# LEDs_and_Buttons.net
KiCad netlist of a schematic drawn in EAGLE
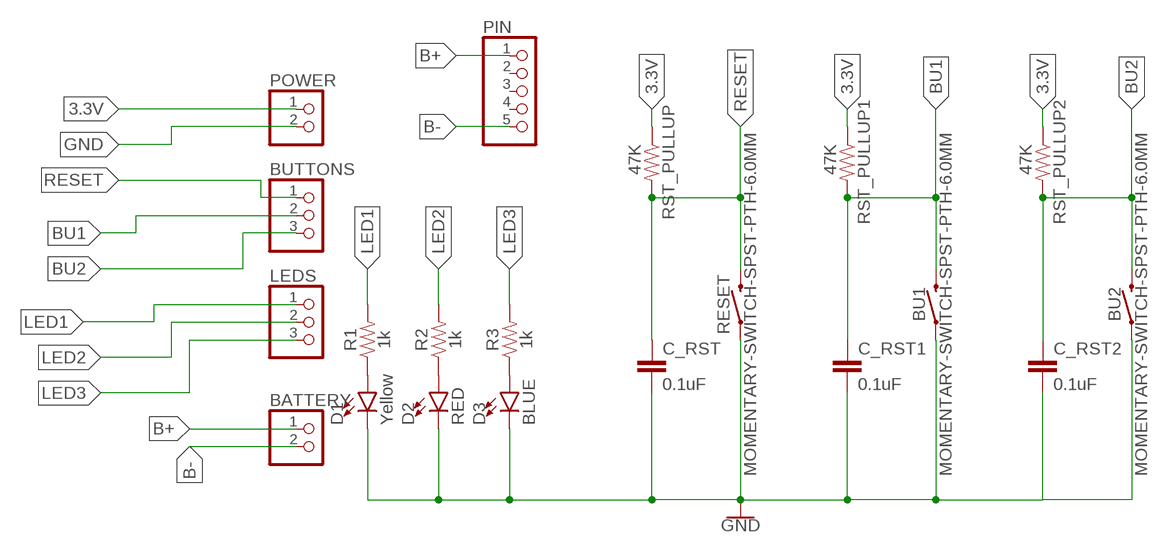
[diagram p0: schematic, sheet 1]

(export (version "E")
  (design (tool "Eeschema 10.0.6"))
  (components
    (comp (ref "BATTERY")
      (value "PINHD-1X2")
      (footprint "eagle-import:1X02")
      (libsource (lib "eagle-import") (part "PINHD-1X2"))
    )
    (comp (ref "BU1")
      (value "MOMENTARY-SWITCH-SPST-PTH-6.0MM")
      (footprint "eagle-import:TACTILE_SWITCH_PTH_6.0MM")
      (libsource (lib "eagle-import") (part "MOMENTARY-SWITCH-SPST-PTH-6.0MM"))
    )
    (comp (ref "BU2")
      (value "MOMENTARY-SWITCH-SPST-PTH-6.0MM")
      (footprint "eagle-import:TACTILE_SWITCH_PTH_6.0MM")
      (libsource (lib "eagle-import") (part "MOMENTARY-SWITCH-SPST-PTH-6.0MM"))
    )
    (comp (ref "BUTTONS")
      (value "PINHD-1X3")
      (footprint "eagle-import:1X03")
      (libsource (lib "eagle-import") (part "PINHD-1X3"))
    )
    (comp (ref "C_RST")
      (value "0.1uF")
      (footprint "eagle-import:0805")
      (libsource (lib "eagle-import") (part "22UF-0805-6.3V-20%"))
    )
    (comp (ref "C_RST1")
      (value "0.1uF")
      (footprint "eagle-import:0805")
      (libsource (lib "eagle-import") (part "22UF-0805-6.3V-20%"))
    )
    (comp (ref "C_RST2")
      (value "0.1uF")
      (footprint "eagle-import:0805")
      (libsource (lib "eagle-import") (part "22UF-0805-6.3V-20%"))
    )
    (comp (ref "D1")
      (value "Yellow")
      (footprint "eagle-import:LED-1206")
      (libsource (lib "eagle-import") (part "LED-YELLOWLILYPAD"))
    )
    (comp (ref "D2")
      (value "RED")
      (footprint "eagle-import:LED-1206")
      (libsource (lib "eagle-import") (part "LED-RED1206"))
    )
    (comp (ref "D3")
      (value "BLUE")
      (footprint "eagle-import:LED-1206")
      (libsource (lib "eagle-import") (part "LED-BLUE1206"))
    )
    (comp (ref "LEDS")
      (value "PINHD-1X3")
      (footprint "eagle-import:1X03")
      (libsource (lib "eagle-import") (part "PINHD-1X3"))
    )
    (comp (ref "PIN")
      (value "PINHD-1X55X2MM")
      (footprint "eagle-import:1_05X2MM")
      (libsource (lib "eagle-import") (part "PINHD-1X55X2MM"))
    )
    (comp (ref "POWER")
      (value "PINHD-1X2")
      (footprint "eagle-import:1X02")
      (libsource (lib "eagle-import") (part "PINHD-1X2"))
    )
    (comp (ref "R1")
      (value "1k")
      (footprint "eagle-import:0805")
      (libsource (lib "eagle-import") (part "0.75OHM-0805-1/4W-1%"))
    )
    (comp (ref "R2")
      (value "1k")
      (footprint "eagle-import:0805")
      (libsource (lib "eagle-import") (part "0.75OHM-0805-1/4W-1%"))
    )
    (comp (ref "R3")
      (value "1k")
      (footprint "eagle-import:0805")
      (libsource (lib "eagle-import") (part "0.75OHM-0805-1/4W-1%"))
    )
    (comp (ref "RESET")
      (value "MOMENTARY-SWITCH-SPST-PTH-6.0MM")
      (footprint "eagle-import:TACTILE_SWITCH_PTH_6.0MM")
      (libsource (lib "eagle-import") (part "MOMENTARY-SWITCH-SPST-PTH-6.0MM"))
    )
    (comp (ref "RST_PULLUP")
      (value "47K")
      (footprint "eagle-import:0805")
      (libsource (lib "eagle-import") (part "RESISTOR0805"))
    )
    (comp (ref "RST_PULLUP1")
      (value "47K")
      (footprint "eagle-import:0805")
      (libsource (lib "eagle-import") (part "RESISTOR0805"))
    )
    (comp (ref "RST_PULLUP2")
      (value "47K")
      (footprint "eagle-import:0805")
      (libsource (lib "eagle-import") (part "RESISTOR0805"))
    )
  )
  (nets
    (net (code "1") (name "3.3V") (class "Default")
      (node (ref "POWER") (pin "1") (pinfunction "1_1") (pintype "passive"))
      (node (ref "RST_PULLUP") (pin "1") (pinfunction "1_1") (pintype "passive"))
      (node (ref "RST_PULLUP1") (pin "1") (pinfunction "1_1") (pintype "passive"))
      (node (ref "RST_PULLUP2") (pin "1") (pinfunction "1_1") (pintype "passive"))
    )
    (net (code "2") (name "B+") (class "Default")
      (node (ref "BATTERY") (pin "1") (pinfunction "1_1") (pintype "passive"))
      (node (ref "PIN") (pin "1") (pinfunction "1_1") (pintype "passive"))
    )
    (net (code "3") (name "B-") (class "Default")
      (node (ref "BATTERY") (pin "2") (pinfunction "2_2") (pintype "passive"))
      (node (ref "PIN") (pin "5") (pinfunction "5_5") (pintype "passive"))
    )
    (net (code "4") (name "BU1") (class "Default")
      (node (ref "BU1") (pin "3") (pinfunction "2_3") (pintype "passive"))
      (node (ref "BUTTONS") (pin "2") (pinfunction "2_2") (pintype "passive"))
      (node (ref "C_RST1") (pin "1") (pinfunction "1_1") (pintype "passive"))
      (node (ref "RST_PULLUP1") (pin "2") (pinfunction "2_2") (pintype "passive"))
    )
    (net (code "5") (name "BU2") (class "Default")
      (node (ref "BU2") (pin "3") (pinfunction "2_3") (pintype "passive"))
      (node (ref "BUTTONS") (pin "3") (pinfunction "3_3") (pintype "passive"))
      (node (ref "C_RST2") (pin "1") (pinfunction "1_1") (pintype "passive"))
      (node (ref "RST_PULLUP2") (pin "2") (pinfunction "2_2") (pintype "passive"))
    )
    (net (code "6") (name "GND") (class "Default")
      (node (ref "BU1") (pin "1") (pinfunction "1_1") (pintype "passive"))
      (node (ref "BU2") (pin "1") (pinfunction "1_1") (pintype "passive"))
      (node (ref "C_RST") (pin "2") (pinfunction "2_2") (pintype "passive"))
      (node (ref "C_RST1") (pin "2") (pinfunction "2_2") (pintype "passive"))
      (node (ref "C_RST2") (pin "2") (pinfunction "2_2") (pintype "passive"))
      (node (ref "D1") (pin "C") (pinfunction "C_C") (pintype "passive"))
      (node (ref "D2") (pin "C") (pinfunction "C_C") (pintype "passive"))
      (node (ref "D3") (pin "C") (pinfunction "C_C") (pintype "passive"))
      (node (ref "POWER") (pin "2") (pinfunction "2_2") (pintype "passive"))
      (node (ref "RESET") (pin "1") (pinfunction "1_1") (pintype "passive"))
    )
    (net (code "7") (name "LED1") (class "Default")
      (node (ref "LEDS") (pin "1") (pinfunction "1_1") (pintype "passive"))
      (node (ref "R1") (pin "2") (pinfunction "2_2") (pintype "passive"))
    )
    (net (code "8") (name "LED2") (class "Default")
      (node (ref "LEDS") (pin "2") (pinfunction "2_2") (pintype "passive"))
      (node (ref "R2") (pin "2") (pinfunction "2_2") (pintype "passive"))
    )
    (net (code "9") (name "LED3") (class "Default")
      (node (ref "LEDS") (pin "3") (pinfunction "3_3") (pintype "passive"))
      (node (ref "R3") (pin "2") (pinfunction "2_2") (pintype "passive"))
    )
    (net (code "10") (name "Net-(D1-PadA)") (class "Default")
      (node (ref "D1") (pin "A") (pinfunction "A_A") (pintype "passive"))
      (node (ref "R1") (pin "1") (pinfunction "1_1") (pintype "passive"))
    )
    (net (code "11") (name "Net-(D2-PadA)") (class "Default")
      (node (ref "D2") (pin "A") (pinfunction "A_A") (pintype "passive"))
      (node (ref "R2") (pin "1") (pinfunction "1_1") (pintype "passive"))
    )
    (net (code "12") (name "Net-(D3-PadA)") (class "Default")
      (node (ref "D3") (pin "A") (pinfunction "A_A") (pintype "passive"))
      (node (ref "R3") (pin "1") (pinfunction "1_1") (pintype "passive"))
    )
    (net (code "13") (name "RESET") (class "Default")
      (node (ref "BUTTONS") (pin "1") (pinfunction "1_1") (pintype "passive"))
      (node (ref "C_RST") (pin "1") (pinfunction "1_1") (pintype "passive"))
      (node (ref "RESET") (pin "3") (pinfunction "2_3") (pintype "passive"))
      (node (ref "RST_PULLUP") (pin "2") (pinfunction "2_2") (pintype "passive"))
    )
    (net (code "14") (name "unconnected-(PIN-Pad2)") (class "Default")
      (node (ref "PIN") (pin "2") (pinfunction "2_2") (pintype "passive"))
    )
    (net (code "15") (name "unconnected-(PIN-Pad3)") (class "Default")
      (node (ref "PIN") (pin "3") (pinfunction "3_3") (pintype "passive"))
    )
    (net (code "16") (name "unconnected-(PIN-Pad4)") (class "Default")
      (node (ref "PIN") (pin "4") (pinfunction "4_4") (pintype "passive"))
    )
  )
)
